# Power_Distribution_-_IO_Expander.net
KiCad netlist of a schematic drawn in Altium Designer
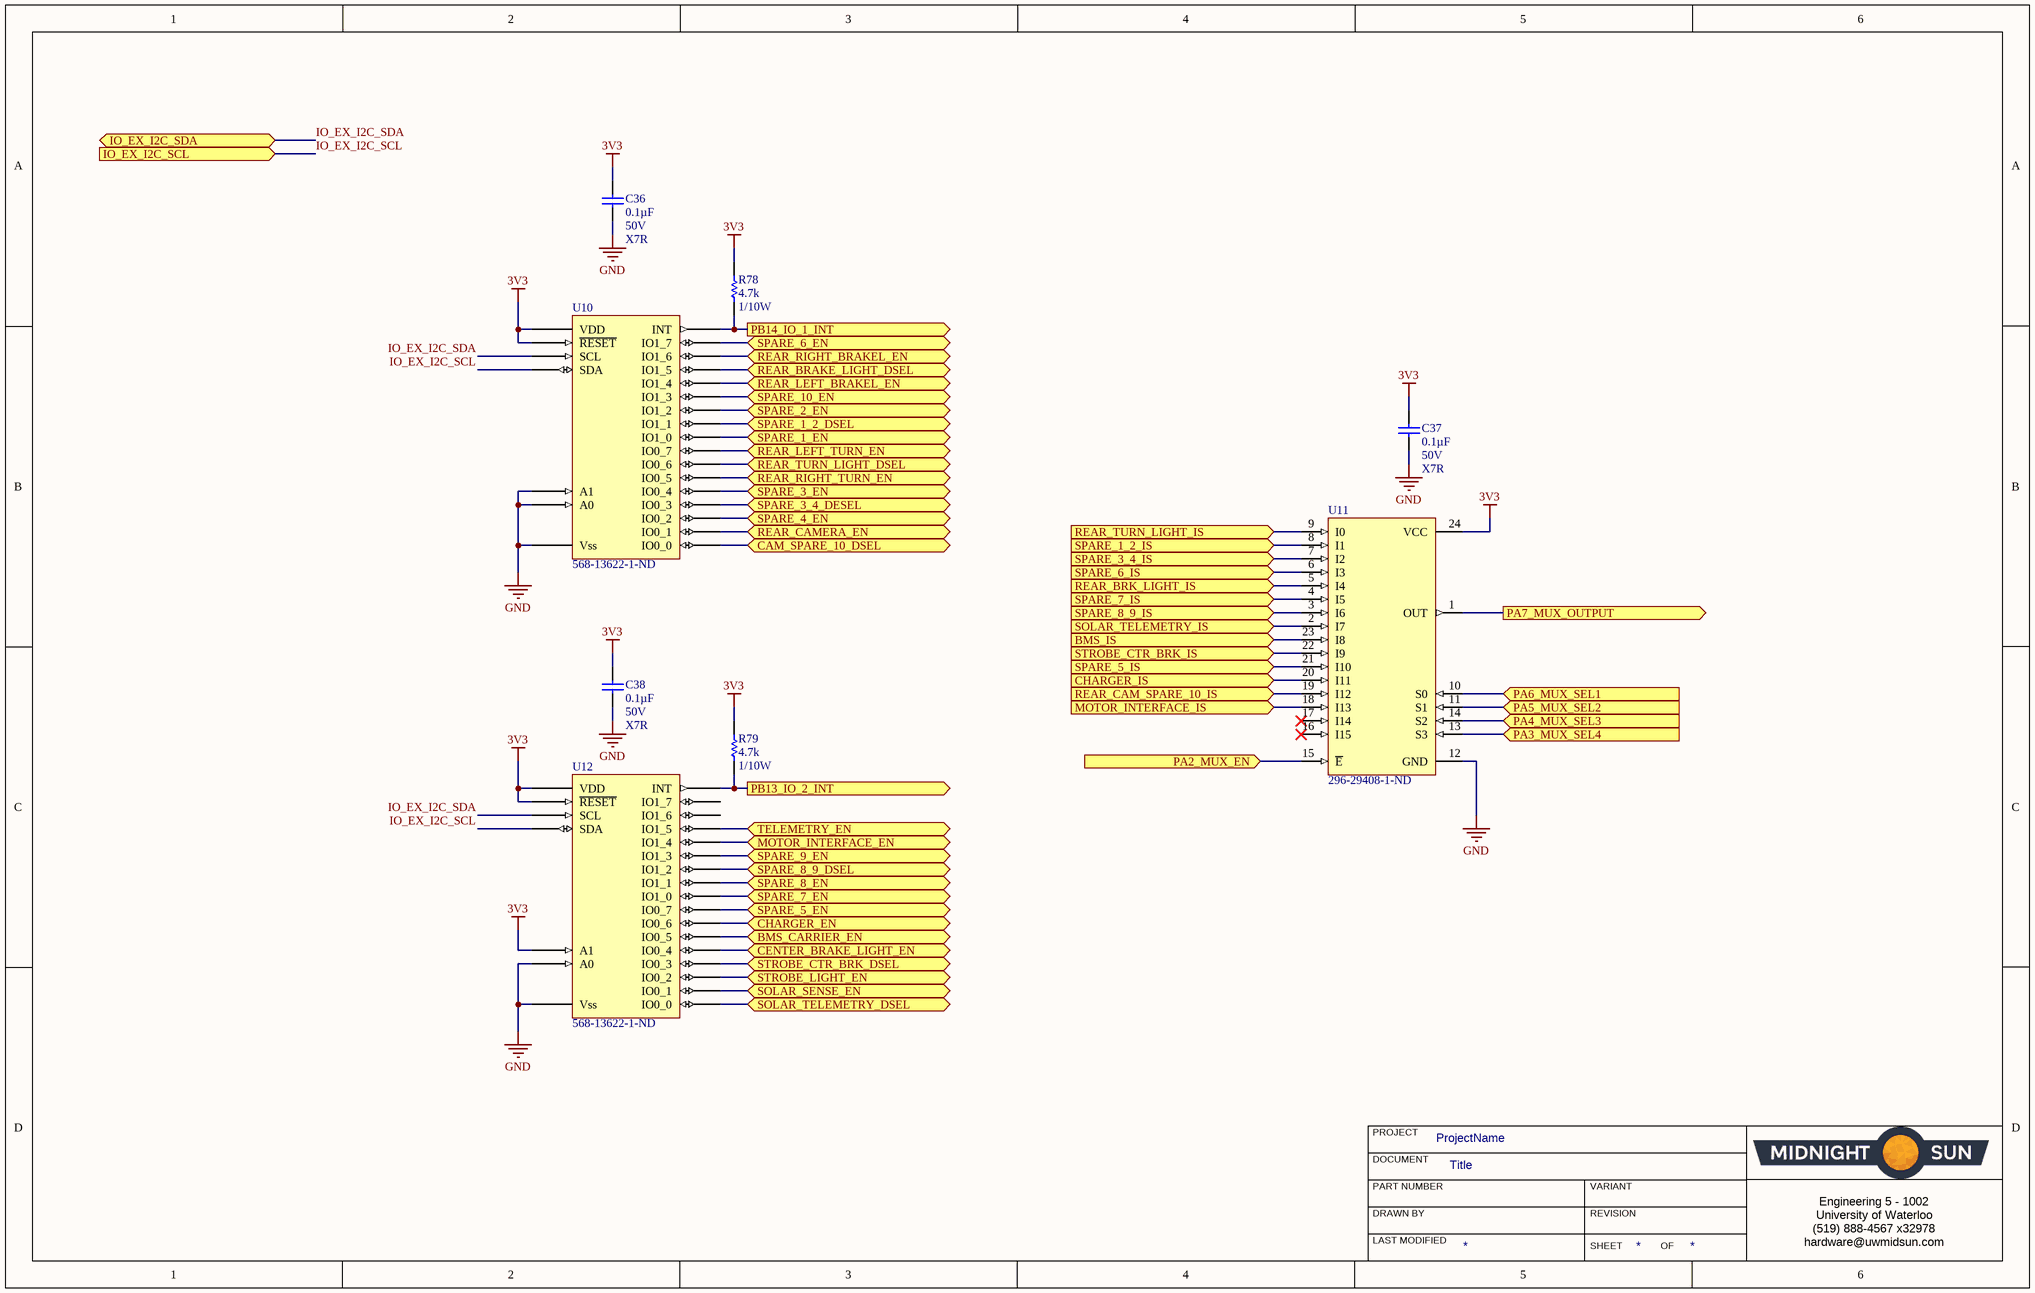
[diagram p0: Power Distribution - IO Expander.SchDoc]

(export (version "E")
  (design (tool "Eeschema 10.0.6"))
  (components
    (comp (ref "C36")
      (value "CAP CER 0.1UF 50V 10% X7R 0603")
      (footprint "CAP, 0603")
      (description "0.10µF ±10% 50V Ceramic Capacitor X7R 0603 (1608 Metric)")
      (fields
        (field (name "TOLERANCE") "±10%")
        (field (name "CAPACITANCE") "0.1µF")
        (field (name "VOLTAGE") "50V")
        (field (name "TEMPERATURE COEFFICIENT") "X7R")
      )
      (libsource (lib "Schematic Diagrams") (part "CAP CER 0.1UF 50V 10% X7R 0603"))
    )
    (comp (ref "C37")
      (value "CAP CER 0.1UF 50V 10% X7R 0603")
      (footprint "CAP, 0603")
      (description "0.10µF ±10% 50V Ceramic Capacitor X7R 0603 (1608 Metric)")
      (fields
        (field (name "TOLERANCE") "±10%")
        (field (name "CAPACITANCE") "0.1µF")
        (field (name "VOLTAGE") "50V")
        (field (name "TEMPERATURE COEFFICIENT") "X7R")
      )
      (libsource (lib "Schematic Diagrams") (part "CAP CER 0.1UF 50V 10% X7R 0603"))
    )
    (comp (ref "C38")
      (value "CAP CER 0.1UF 50V 10% X7R 0603")
      (footprint "CAP, 0603")
      (description "0.10µF ±10% 50V Ceramic Capacitor X7R 0603 (1608 Metric)")
      (fields
        (field (name "TOLERANCE") "±10%")
        (field (name "CAPACITANCE") "0.1µF")
        (field (name "VOLTAGE") "50V")
        (field (name "TEMPERATURE COEFFICIENT") "X7R")
      )
      (libsource (lib "Schematic Diagrams") (part "CAP CER 0.1UF 50V 10% X7R 0603"))
    )
    (comp (ref "R78")
      (value "RES 4.7K OHM 1% 1/10W 0603")
      (footprint "RES, 0603")
      (description "4.7k Ohm ±1% 0.1W, 1/10W Chip Resistor 0603 (1608 Metric) Moisture Resistant Thick Film")
      (fields
        (field (name "TOLERANCE") "±1%")
        (field (name "RESISTANCE (OHMS)") "4.7k")
        (field (name "POWER (WATTS)") "1/10W")
      )
      (libsource (lib "Schematic Diagrams") (part "RES 4.7K OHM 1% 1/10W 0603"))
    )
    (comp (ref "R79")
      (value "RES 4.7K OHM 1% 1/10W 0603")
      (footprint "RES, 0603")
      (description "4.7k Ohm ±1% 0.1W, 1/10W Chip Resistor 0603 (1608 Metric) Moisture Resistant Thick Film")
      (fields
        (field (name "TOLERANCE") "±1%")
        (field (name "RESISTANCE (OHMS)") "4.7k")
        (field (name "POWER (WATTS)") "1/10W")
      )
      (libsource (lib "Schematic Diagrams") (part "RES 4.7K OHM 1% 1/10W 0603"))
    )
    (comp (ref "U10")
      (value "16-BIT I2C-BUS AND SMBUS LOW POW")
      (footprint "SOP127P600-8N")
      (description "I/O Expander 16 I²C, SMBus 400kHz 24-TSSOP")
      (fields (field (name "SUPPLIER PART NUMBER 1") "568-13622-1-ND"))
      (libsource (lib "Schematic Diagrams") (part "16-BIT I2C-BUS AND SMBUS LOW POW"))
    )
    (comp (ref "U11")
      (value "IC MUX/DEMUX 1X16 24SSOP")
      (footprint "SOP127P1030X265-24N")
      (description "1 Circuit IC Switch 16:1 160 Ohm 24-SOIC")
      (fields
        (field (name "MANUFACTURER") "Texas Instruments")
        (field (name "MANUFACTURER PART NUMBER") "CD74HC4067M96")
        (field (name "SUPPLIER PART NUMBER 1") "296-29408-1-ND")
      )
      (libsource (lib "Schematic Diagrams") (part "IC MUX/DEMUX 1X16 24SSOP"))
    )
    (comp (ref "U12")
      (value "16-BIT I2C-BUS AND SMBUS LOW POW")
      (footprint "SOP127P600-8N")
      (description "I/O Expander 16 I²C, SMBus 400kHz 24-TSSOP")
      (fields (field (name "SUPPLIER PART NUMBER 1") "568-13622-1-ND"))
      (libsource (lib "Schematic Diagrams") (part "16-BIT I2C-BUS AND SMBUS LOW POW"))
    )
  )
  (nets
    (net (code "1") (name "/BMS_CARRIER_EN") (class "Default")
      (node (ref "U12") (pin "9") (pinfunction "IO0_5_9") (pintype "bidirectional"))
    )
    (net (code "2") (name "/BMS_IS") (class "Default")
      (node (ref "U11") (pin "23") (pinfunction "I8_23") (pintype "input"))
    )
    (net (code "3") (name "/CAM_SPARE_10_DSEL") (class "Default")
      (node (ref "U10") (pin "4") (pinfunction "IO0_0_4") (pintype "bidirectional"))
    )
    (net (code "4") (name "/CENTER_BRAKE_LIGHT_EN") (class "Default")
      (node (ref "U12") (pin "8") (pinfunction "IO0_4_8") (pintype "bidirectional"))
    )
    (net (code "5") (name "/CHARGER_EN") (class "Default")
      (node (ref "U12") (pin "10") (pinfunction "IO0_6_10") (pintype "bidirectional"))
    )
    (net (code "6") (name "/CHARGER_IS") (class "Default")
      (node (ref "U11") (pin "20") (pinfunction "I11_20") (pintype "input"))
    )
    (net (code "7") (name "/IO_EX_I2C_SCL") (class "Default")
      (node (ref "U10") (pin "23") (pinfunction "SDA_23") (pintype "bidirectional"))
      (node (ref "U12") (pin "23") (pinfunction "SDA_23") (pintype "bidirectional"))
    )
    (net (code "8") (name "/IO_EX_I2C_SDA") (class "Default")
      (node (ref "U10") (pin "22") (pinfunction "SCL_22") (pintype "input"))
      (node (ref "U12") (pin "22") (pinfunction "SCL_22") (pintype "input"))
    )
    (net (code "9") (name "/MOTOR_INTERFACE_EN") (class "Default")
      (node (ref "U12") (pin "17") (pinfunction "IO1_4_17") (pintype "bidirectional"))
    )
    (net (code "10") (name "/MOTOR_INTERFACE_IS") (class "Default")
      (node (ref "U11") (pin "18") (pinfunction "I13_18") (pintype "input"))
    )
    (net (code "11") (name "/PA2_MUX_EN") (class "Default")
      (node (ref "U11") (pin "15") (pinfunction "~{E}_15") (pintype "input"))
    )
    (net (code "12") (name "/PA3_MUX_SEL4") (class "Default")
      (node (ref "U11") (pin "13") (pinfunction "S3_13") (pintype "input"))
    )
    (net (code "13") (name "/PA4_MUX_SEL3") (class "Default")
      (node (ref "U11") (pin "14") (pinfunction "S2_14") (pintype "input"))
    )
    (net (code "14") (name "/PA5_MUX_SEL2") (class "Default")
      (node (ref "U11") (pin "11") (pinfunction "S1_11") (pintype "input"))
    )
    (net (code "15") (name "/PA6_MUX_SEL1") (class "Default")
      (node (ref "U11") (pin "10") (pinfunction "S0_10") (pintype "input"))
    )
    (net (code "16") (name "/PA7_MUX_OUTPUT") (class "Default")
      (node (ref "U11") (pin "1") (pinfunction "OUT_1") (pintype "output"))
    )
    (net (code "17") (name "/PB13_IO_2_INT") (class "Default")
      (node (ref "R79") (pin "2") (pinfunction "2_2") (pintype "passive"))
      (node (ref "U12") (pin "1") (pinfunction "INT_1") (pintype "output"))
    )
    (net (code "18") (name "/PB14_IO_1_INT") (class "Default")
      (node (ref "R78") (pin "2") (pinfunction "2_2") (pintype "passive"))
      (node (ref "U10") (pin "1") (pinfunction "INT_1") (pintype "output"))
    )
    (net (code "19") (name "/REAR_BRAKE_LIGHT_DSEL") (class "Default")
      (node (ref "U10") (pin "18") (pinfunction "IO1_5_18") (pintype "bidirectional"))
    )
    (net (code "20") (name "/REAR_BRK_LIGHT_IS") (class "Default")
      (node (ref "U11") (pin "5") (pinfunction "I4_5") (pintype "input"))
    )
    (net (code "21") (name "/REAR_CAMERA_EN") (class "Default")
      (node (ref "U10") (pin "5") (pinfunction "IO0_1_5") (pintype "bidirectional"))
    )
    (net (code "22") (name "/REAR_CAM_SPARE_10_IS") (class "Default")
      (node (ref "U11") (pin "19") (pinfunction "I12_19") (pintype "input"))
    )
    (net (code "23") (name "/REAR_LEFT_BRAKEL_EN") (class "Default")
      (node (ref "U10") (pin "17") (pinfunction "IO1_4_17") (pintype "bidirectional"))
    )
    (net (code "24") (name "/REAR_LEFT_TURN_EN") (class "Default")
      (node (ref "U10") (pin "11") (pinfunction "IO0_7_11") (pintype "bidirectional"))
    )
    (net (code "25") (name "/REAR_RIGHT_BRAKEL_EN") (class "Default")
      (node (ref "U10") (pin "19") (pinfunction "IO1_6_19") (pintype "bidirectional"))
    )
    (net (code "26") (name "/REAR_RIGHT_TURN_EN") (class "Default")
      (node (ref "U10") (pin "9") (pinfunction "IO0_5_9") (pintype "bidirectional"))
    )
    (net (code "27") (name "/REAR_TURN_LIGHT_DSEL") (class "Default")
      (node (ref "U10") (pin "10") (pinfunction "IO0_6_10") (pintype "bidirectional"))
    )
    (net (code "28") (name "/REAR_TURN_LIGHT_IS") (class "Default")
      (node (ref "U11") (pin "9") (pinfunction "I0_9") (pintype "input"))
    )
    (net (code "29") (name "/SOLAR_SENSE_EN") (class "Default")
      (node (ref "U12") (pin "5") (pinfunction "IO0_1_5") (pintype "bidirectional"))
    )
    (net (code "30") (name "/SOLAR_TELEMETRY_DSEL") (class "Default")
      (node (ref "U12") (pin "4") (pinfunction "IO0_0_4") (pintype "bidirectional"))
    )
    (net (code "31") (name "/SOLAR_TELEMETRY_IS") (class "Default")
      (node (ref "U11") (pin "2") (pinfunction "I7_2") (pintype "input"))
    )
    (net (code "32") (name "/SPARE_1_2_DSEL") (class "Default")
      (node (ref "U10") (pin "14") (pinfunction "IO1_1_14") (pintype "bidirectional"))
    )
    (net (code "33") (name "/SPARE_1_2_IS") (class "Default")
      (node (ref "U11") (pin "8") (pinfunction "I1_8") (pintype "input"))
    )
    (net (code "34") (name "/SPARE_1_EN") (class "Default")
      (node (ref "U10") (pin "13") (pinfunction "IO1_0_13") (pintype "bidirectional"))
    )
    (net (code "35") (name "/SPARE_2_EN") (class "Default")
      (node (ref "U10") (pin "15") (pinfunction "IO1_2_15") (pintype "bidirectional"))
    )
    (net (code "36") (name "/SPARE_3_4_DESEL") (class "Default")
      (node (ref "U10") (pin "7") (pinfunction "IO0_3_7") (pintype "bidirectional"))
    )
    (net (code "37") (name "/SPARE_3_4_IS") (class "Default")
      (node (ref "U11") (pin "7") (pinfunction "I2_7") (pintype "input"))
    )
    (net (code "38") (name "/SPARE_3_EN") (class "Default")
      (node (ref "U10") (pin "8") (pinfunction "IO0_4_8") (pintype "bidirectional"))
    )
    (net (code "39") (name "/SPARE_4_EN") (class "Default")
      (node (ref "U10") (pin "6") (pinfunction "IO0_2_6") (pintype "bidirectional"))
    )
    (net (code "40") (name "/SPARE_5_EN") (class "Default")
      (node (ref "U12") (pin "11") (pinfunction "IO0_7_11") (pintype "bidirectional"))
    )
    (net (code "41") (name "/SPARE_5_IS") (class "Default")
      (node (ref "U11") (pin "21") (pinfunction "I10_21") (pintype "input"))
    )
    (net (code "42") (name "/SPARE_6_EN") (class "Default")
      (node (ref "U10") (pin "20") (pinfunction "IO1_7_20") (pintype "bidirectional"))
    )
    (net (code "43") (name "/SPARE_6_IS") (class "Default")
      (node (ref "U11") (pin "6") (pinfunction "I3_6") (pintype "input"))
    )
    (net (code "44") (name "/SPARE_7_EN") (class "Default")
      (node (ref "U12") (pin "13") (pinfunction "IO1_0_13") (pintype "bidirectional"))
    )
    (net (code "45") (name "/SPARE_7_IS") (class "Default")
      (node (ref "U11") (pin "4") (pinfunction "I5_4") (pintype "input"))
    )
    (net (code "46") (name "/SPARE_8_9_DSEL") (class "Default")
      (node (ref "U12") (pin "15") (pinfunction "IO1_2_15") (pintype "bidirectional"))
    )
    (net (code "47") (name "/SPARE_8_9_IS") (class "Default")
      (node (ref "U11") (pin "3") (pinfunction "I6_3") (pintype "input"))
    )
    (net (code "48") (name "/SPARE_8_EN") (class "Default")
      (node (ref "U12") (pin "14") (pinfunction "IO1_1_14") (pintype "bidirectional"))
    )
    (net (code "49") (name "/SPARE_9_EN") (class "Default")
      (node (ref "U12") (pin "16") (pinfunction "IO1_3_16") (pintype "bidirectional"))
    )
    (net (code "50") (name "/SPARE_10_EN") (class "Default")
      (node (ref "U10") (pin "16") (pinfunction "IO1_3_16") (pintype "bidirectional"))
    )
    (net (code "51") (name "/STROBE_CTR_BRK_DSEL") (class "Default")
      (node (ref "U12") (pin "7") (pinfunction "IO0_3_7") (pintype "bidirectional"))
    )
    (net (code "52") (name "/STROBE_CTR_BRK_IS") (class "Default")
      (node (ref "U11") (pin "22") (pinfunction "I9_22") (pintype "input"))
    )
    (net (code "53") (name "/STROBE_LIGHT_EN") (class "Default")
      (node (ref "U12") (pin "6") (pinfunction "IO0_2_6") (pintype "bidirectional"))
    )
    (net (code "54") (name "/TELEMETRY_EN") (class "Default")
      (node (ref "U12") (pin "18") (pinfunction "IO1_5_18") (pintype "bidirectional"))
    )
    (net (code "55") (name "3V3") (class "Default")
      (node (ref "C36") (pin "1") (pinfunction "1_1") (pintype "passive"))
      (node (ref "C37") (pin "1") (pinfunction "1_1") (pintype "passive"))
      (node (ref "C38") (pin "1") (pinfunction "1_1") (pintype "passive"))
      (node (ref "R78") (pin "1") (pinfunction "1_1") (pintype "passive"))
      (node (ref "R79") (pin "1") (pinfunction "1_1") (pintype "passive"))
      (node (ref "U10") (pin "24") (pinfunction "VDD_24") (pintype "power_in"))
      (node (ref "U10") (pin "3") (pinfunction "~{RESET}_3") (pintype "input"))
      (node (ref "U11") (pin "24") (pinfunction "VCC_24") (pintype "power_in"))
      (node (ref "U12") (pin "2") (pinfunction "A1_2") (pintype "input"))
      (node (ref "U12") (pin "24") (pinfunction "VDD_24") (pintype "power_in"))
      (node (ref "U12") (pin "3") (pinfunction "~{RESET}_3") (pintype "input"))
    )
    (net (code "56") (name "GND") (class "Default")
      (node (ref "C36") (pin "2") (pinfunction "2_2") (pintype "passive"))
      (node (ref "C37") (pin "2") (pinfunction "2_2") (pintype "passive"))
      (node (ref "C38") (pin "2") (pinfunction "2_2") (pintype "passive"))
      (node (ref "U10") (pin "12") (pinfunction "Vss_12") (pintype "power_in"))
      (node (ref "U10") (pin "2") (pinfunction "A1_2") (pintype "input"))
      (node (ref "U10") (pin "21") (pinfunction "A0_21") (pintype "input"))
      (node (ref "U11") (pin "12") (pinfunction "GND_12") (pintype "power_in"))
      (node (ref "U12") (pin "12") (pinfunction "Vss_12") (pintype "power_in"))
      (node (ref "U12") (pin "21") (pinfunction "A0_21") (pintype "input"))
    )
    (net (code "57") (name "unconnected-(U11-I14-Pad17)") (class "Default")
      (node (ref "U11") (pin "17") (pinfunction "I14_17") (pintype "input+no_connect"))
    )
    (net (code "58") (name "unconnected-(U11-I15-Pad16)") (class "Default")
      (node (ref "U11") (pin "16") (pinfunction "I15_16") (pintype "input+no_connect"))
    )
    (net (code "59") (name "unconnected-(U12-IO1_6-Pad19)") (class "Default")
      (node (ref "U12") (pin "19") (pinfunction "IO1_6_19") (pintype "bidirectional"))
    )
    (net (code "60") (name "unconnected-(U12-IO1_7-Pad20)") (class "Default")
      (node (ref "U12") (pin "20") (pinfunction "IO1_7_20") (pintype "bidirectional"))
    )
  )
)
